# 1_TSAL_Green.net
KiCad netlist of a schematic drawn in Altium Designer
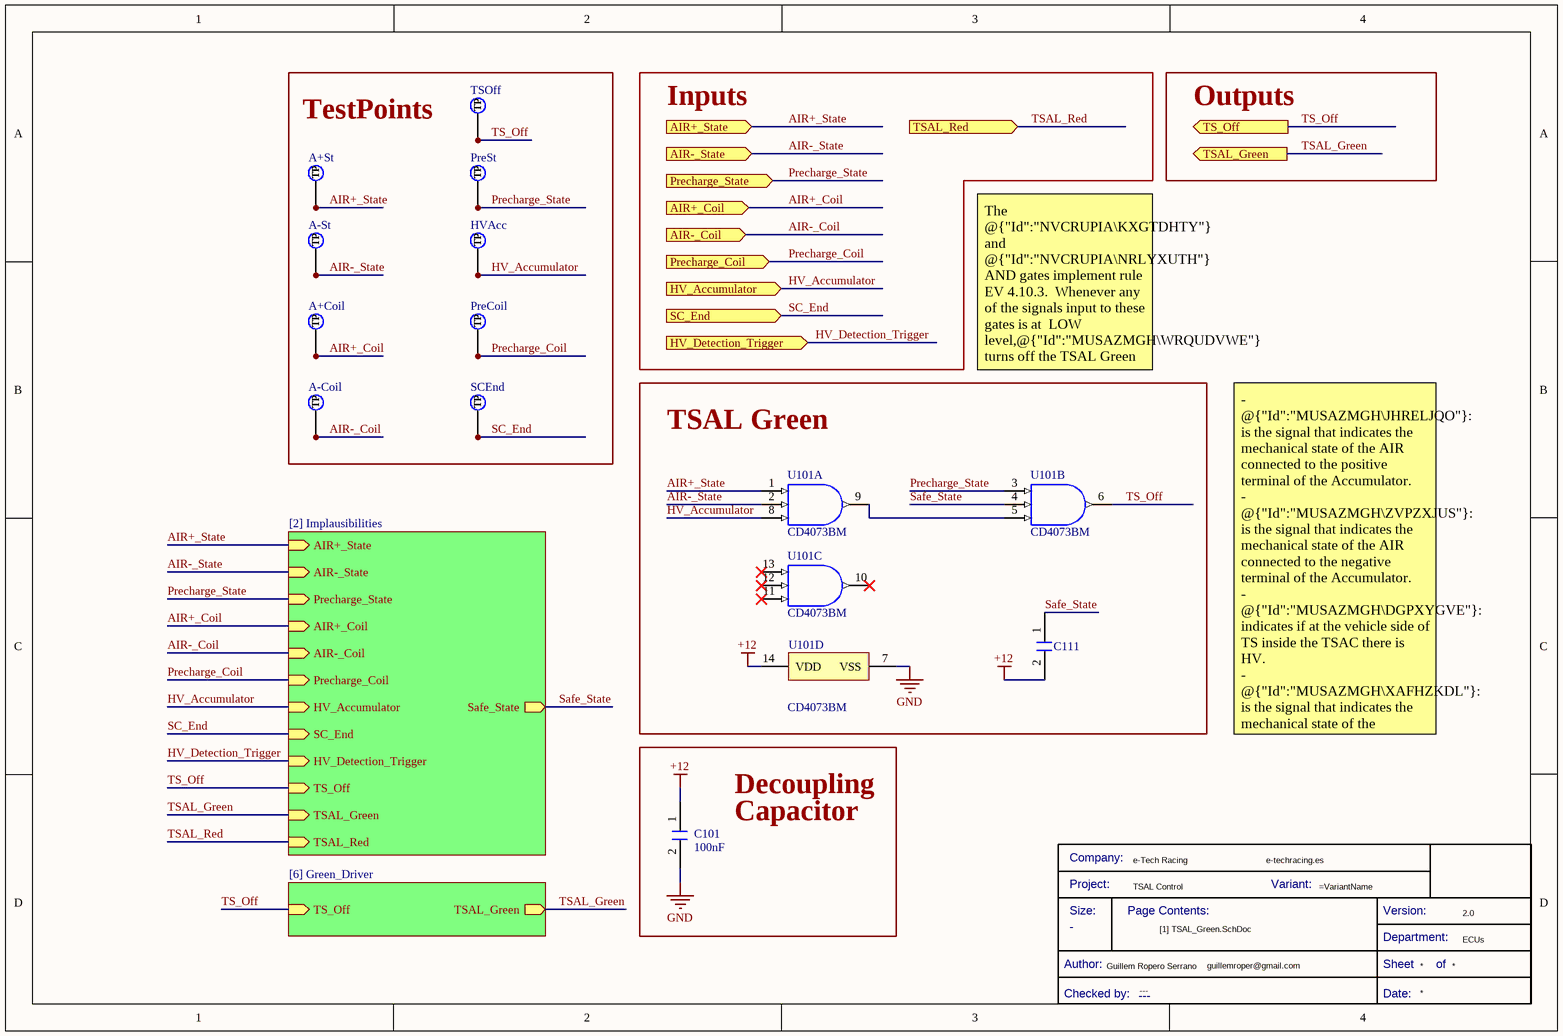
[diagram p0: [1] TSAL_Green.SchDoc]

(export (version "E")
  (design (tool "Eeschema 10.0.6"))
  (components
    (comp (ref "A+Coil")
      (value "TestPoint")
      (footprint "TestPoint")
      (description "Test Point 1x1 mm")
      (fields (field (name ".SCHCHECK") "GP") (field (name ".CREATOR") "GP") (field (name ".PCBCHECK") "GP"))
      (libsource (lib "EMEA- E-Tech Racing- I'Escola d'Enginyeria de Barcelona Est") (part "TestPoint"))
    )
    (comp (ref "A+St")
      (value "TestPoint")
      (footprint "TestPoint")
      (description "Test Point 1x1 mm")
      (fields (field (name ".SCHCHECK") "GP") (field (name ".CREATOR") "GP") (field (name ".PCBCHECK") "GP"))
      (libsource (lib "EMEA- E-Tech Racing- I'Escola d'Enginyeria de Barcelona Est") (part "TestPoint"))
    )
    (comp (ref "A-Coil")
      (value "TestPoint")
      (footprint "TestPoint")
      (description "Test Point 1x1 mm")
      (fields (field (name ".SCHCHECK") "GP") (field (name ".CREATOR") "GP") (field (name ".PCBCHECK") "GP"))
      (libsource (lib "EMEA- E-Tech Racing- I'Escola d'Enginyeria de Barcelona Est") (part "TestPoint"))
    )
    (comp (ref "A-St")
      (value "TestPoint")
      (footprint "TestPoint")
      (description "Test Point 1x1 mm")
      (fields (field (name ".SCHCHECK") "GP") (field (name ".CREATOR") "GP") (field (name ".PCBCHECK") "GP"))
      (libsource (lib "EMEA- E-Tech Racing- I'Escola d'Enginyeria de Barcelona Est") (part "TestPoint"))
    )
    (comp (ref "C101")
      (value "100nF")
      (footprint "C0805FNPC-R")
      (description "Cap, 0.1ΜF, 50V, 10%, X7R, 0805")
      (fields
        (field (name "TOLERANCE") "10%")
        (field (name "Comment") "C100n-50V-0805FNPC-X7R")
        (field (name ".CREATOR") "DR")
      )
      (libsource (lib "EMEA- E-Tech Racing- I'Escola d'Enginyeria de Barcelona Est") (part "C100p-50V-0805FNPC-C0G/NP0"))
    )
    (comp (ref "C111")
      (value "C15p-50V-0805FNPC-NP0")
      (footprint "C0805FNPC-R")
      (description "Cap, 15PF, 50V, 5%, C0G/NP0, 0805")
      (fields (field (name "TOLERANCE") "5%") (field (name ".CREATOR") "DR"))
      (libsource (lib "EMEA- E-Tech Racing- I'Escola d'Enginyeria de Barcelona Est") (part "C100p-50V-0805FNPC-C0G/NP0"))
    )
    (comp (ref "HVAcc")
      (value "TestPoint")
      (footprint "TestPoint")
      (description "Test Point 1x1 mm")
      (fields (field (name ".SCHCHECK") "GP") (field (name ".CREATOR") "GP") (field (name ".PCBCHECK") "GP"))
      (libsource (lib "EMEA- E-Tech Racing- I'Escola d'Enginyeria de Barcelona Est") (part "TestPoint"))
    )
    (comp (ref "PreCoil")
      (value "TestPoint")
      (footprint "TestPoint")
      (description "Test Point 1x1 mm")
      (fields (field (name ".SCHCHECK") "GP") (field (name ".CREATOR") "GP") (field (name ".PCBCHECK") "GP"))
      (libsource (lib "EMEA- E-Tech Racing- I'Escola d'Enginyeria de Barcelona Est") (part "TestPoint"))
    )
    (comp (ref "PreSt")
      (value "TestPoint")
      (footprint "TestPoint")
      (description "Test Point 1x1 mm")
      (fields (field (name ".SCHCHECK") "GP") (field (name ".CREATOR") "GP") (field (name ".PCBCHECK") "GP"))
      (libsource (lib "EMEA- E-Tech Racing- I'Escola d'Enginyeria de Barcelona Est") (part "TestPoint"))
    )
    (comp (ref "SCEnd")
      (value "TestPoint")
      (footprint "TestPoint")
      (description "Test Point 1x1 mm")
      (fields (field (name ".SCHCHECK") "GP") (field (name ".CREATOR") "GP") (field (name ".PCBCHECK") "GP"))
      (libsource (lib "EMEA- E-Tech Racing- I'Escola d'Enginyeria de Barcelona Est") (part "TestPoint"))
    )
    (comp (ref "TSOff")
      (value "TestPoint")
      (footprint "TestPoint")
      (description "Test Point 1x1 mm")
      (fields (field (name ".SCHCHECK") "GP") (field (name ".CREATOR") "GP") (field (name ".PCBCHECK") "GP"))
      (libsource (lib "EMEA- E-Tech Racing- I'Escola d'Enginyeria de Barcelona Est") (part "TestPoint"))
    )
    (comp (ref "U101")
      (value "CD4073BM")
      (footprint "D0014A_N")
      (description "AND Gate, 4000/14000/40000 Series, 3-Func, 3-Input, CMOS, PDSO14")
      (libsource (lib "EMEA- E-Tech Racing- I'Escola d'Enginyeria de Barcelona Est") (part "TI-CD4073B-14"))
    )
  )
  (nets
    (net (code "1") (name "+12") (class "Default")
      (node (ref "C101") (pin "1") (pinfunction "1_1") (pintype "passive"))
      (node (ref "C111") (pin "2") (pinfunction "2_2") (pintype "passive"))
      (node (ref "U101") (pin "14") (pinfunction "VDD_14") (pintype "power_in"))
    )
    (net (code "2") (name "/AIR+_Coil") (class "Default")
      (node (ref "A+Coil") (pin "1") (pinfunction "TP_1") (pintype "passive"))
    )
    (net (code "3") (name "/AIR+_State") (class "Default")
      (node (ref "A+St") (pin "1") (pinfunction "TP_1") (pintype "passive"))
      (node (ref "U101") (pin "1") (pinfunction "A_1") (pintype "input"))
    )
    (net (code "4") (name "/AIR-_Coil") (class "Default")
      (node (ref "A-Coil") (pin "1") (pinfunction "TP_1") (pintype "passive"))
    )
    (net (code "5") (name "/AIR-_State") (class "Default")
      (node (ref "A-St") (pin "1") (pinfunction "TP_1") (pintype "passive"))
      (node (ref "U101") (pin "2") (pinfunction "B_2") (pintype "input"))
    )
    (net (code "6") (name "/HV_Accumulator") (class "Default")
      (node (ref "HVAcc") (pin "1") (pinfunction "TP_1") (pintype "passive"))
      (node (ref "U101") (pin "8") (pinfunction "C_8") (pintype "input"))
    )
    (net (code "8") (name "/Precharge_Coil") (class "Default")
      (node (ref "PreCoil") (pin "1") (pinfunction "TP_1") (pintype "passive"))
    )
    (net (code "9") (name "/Precharge_State") (class "Default")
      (node (ref "PreSt") (pin "1") (pinfunction "TP_1") (pintype "passive"))
      (node (ref "U101") (pin "3") (pinfunction "D_3") (pintype "input"))
    )
    (net (code "10") (name "/SC_End") (class "Default")
      (node (ref "SCEnd") (pin "1") (pinfunction "TP_1") (pintype "passive"))
    )
    (net (code "11") (name "/Safe_State") (class "Default")
      (node (ref "C111") (pin "1") (pinfunction "1_1") (pintype "passive"))
      (node (ref "U101") (pin "4") (pinfunction "E_4") (pintype "input"))
    )
    (net (code "14") (name "/TS_Off") (class "Default")
      (node (ref "TSOff") (pin "1") (pinfunction "TP_1") (pintype "passive"))
      (node (ref "U101") (pin "6") (pinfunction "K_6") (pintype "output"))
    )
    (net (code "15") (name "GND") (class "Default")
      (node (ref "C101") (pin "2") (pinfunction "2_2") (pintype "passive"))
      (node (ref "U101") (pin "7") (pinfunction "VSS_7") (pintype "power_in"))
    )
    (net (code "16") (name "Net-(U101A-J)") (class "Default")
      (node (ref "U101") (pin "5") (pinfunction "F_5") (pintype "input"))
      (node (ref "U101") (pin "9") (pinfunction "J_9") (pintype "output"))
    )
    (net (code "17") (name "unconnected-(U101C-G-Pad13)") (class "Default")
      (node (ref "U101") (pin "13") (pinfunction "G_13") (pintype "input+no_connect"))
    )
    (net (code "18") (name "unconnected-(U101C-H-Pad12)") (class "Default")
      (node (ref "U101") (pin "12") (pinfunction "H_12") (pintype "input+no_connect"))
    )
    (net (code "19") (name "unconnected-(U101C-I-Pad11)") (class "Default")
      (node (ref "U101") (pin "11") (pinfunction "I_11") (pintype "input+no_connect"))
    )
    (net (code "20") (name "unconnected-(U101C-L-Pad10)") (class "Default")
      (node (ref "U101") (pin "10") (pinfunction "L_10") (pintype "output+no_connect"))
    )
  )
)
